# CSI2-IMX8M-EVK-2_Rev02.net
KiCad netlist of a schematic drawn in Altium Designer
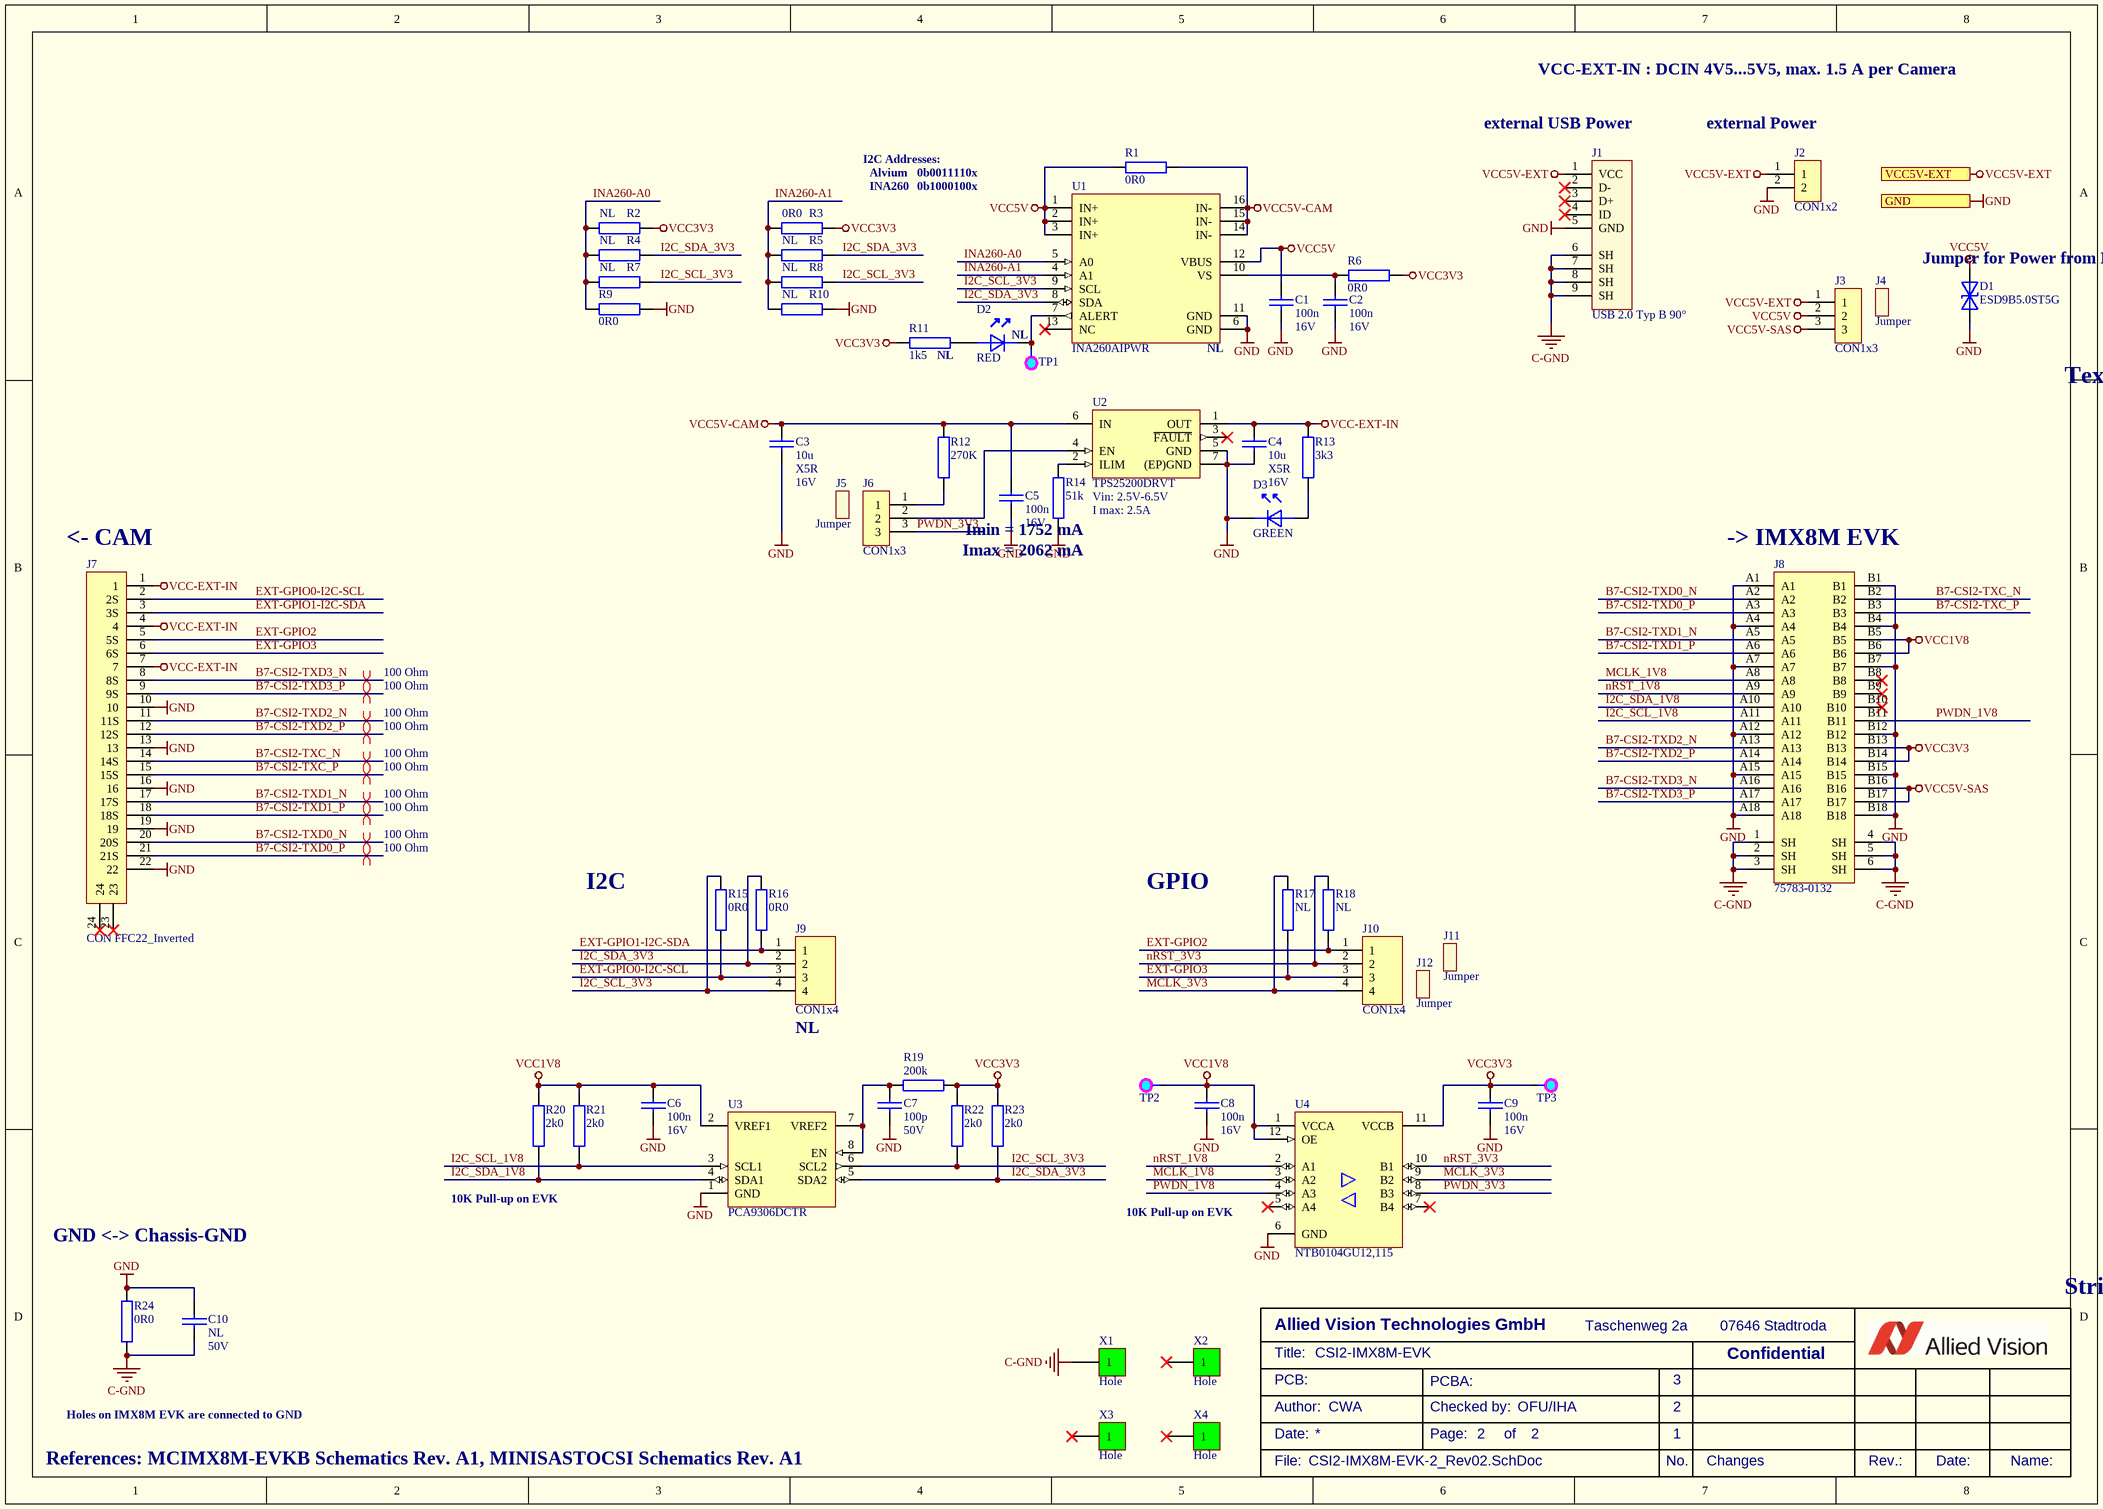
[diagram p0: CSI2-IMX8M-EVK-2_Rev02.SchDoc]

(export (version "E")
  (design (tool "Eeschema 10.0.6"))
  (components
    (comp (ref "C1")
      (value "100n")
      (footprint "C-0402_0.55")
      (description "Capacitor Ceramic SMD/0402/16V/X7R/10%")
      (fields
        (field (name "KHK PART NUMBER") "K8340114")
        (field (name "MANUFACTURER") "several")
        (field (name "VOLTAGE") "16V")
      )
      (libsource (lib "Passive") (part "C 100N 10% 16V X7R 402"))
    )
    (comp (ref "C2")
      (value "100n")
      (footprint "C-0402_0.55")
      (description "Capacitor Ceramic SMD/0402/16V/X7R/10%")
      (fields
        (field (name "KHK PART NUMBER") "K8340114")
        (field (name "MANUFACTURER") "several")
        (field (name "VOLTAGE") "16V")
      )
      (libsource (lib "Passive") (part "C 100N 10% 16V X7R 402"))
    )
    (comp (ref "C3")
      (value "10u")
      (footprint "C-0805_1.4")
      (description "Capacitor Ceramic SMD/0805/16V/X5R/10%")
      (fields
        (field (name "KHK PART NUMBER") "K8340151")
        (field (name "MANUFACTURER") "several")
        (field (name "DIELECTRIC") "X5R")
        (field (name "VOLTAGE") "16V")
      )
      (libsource (lib "Passive") (part "C 10U 16V X5R 0805"))
    )
    (comp (ref "C4")
      (value "10u")
      (footprint "C-0805_1.4")
      (description "Capacitor Ceramic SMD/0805/16V/X5R/10%")
      (fields
        (field (name "KHK PART NUMBER") "K8340151")
        (field (name "MANUFACTURER") "several")
        (field (name "DIELECTRIC") "X5R")
        (field (name "VOLTAGE") "16V")
      )
      (libsource (lib "Passive") (part "C 10U 16V X5R 0805"))
    )
    (comp (ref "C5")
      (value "100n")
      (footprint "C-0402_0.55")
      (description "Capacitor Ceramic SMD/0402/16V/X7R/10%")
      (fields
        (field (name "KHK PART NUMBER") "K8340114")
        (field (name "MANUFACTURER") "several")
        (field (name "VOLTAGE") "16V")
      )
      (libsource (lib "Passive") (part "C 100N 10% 16V X7R 402"))
    )
    (comp (ref "C6")
      (value "100n")
      (footprint "C-0402_0.55")
      (description "Capacitor Ceramic SMD/0402/16V/X7R/10%")
      (fields
        (field (name "KHK PART NUMBER") "K8340114")
        (field (name "MANUFACTURER") "several")
        (field (name "VOLTAGE") "16V")
      )
      (libsource (lib "Passive") (part "C 100N 10% 16V X7R 402"))
    )
    (comp (ref "C7")
      (value "100p")
      (footprint "C-0402_0.55")
      (description "Capacitor Ceramic SMD/0402/50V/X7R/10%")
      (fields
        (field (name "KHK PART NUMBER") "K8340145")
        (field (name "MANUFACTURER") "several")
        (field (name "VOLTAGE") "50V")
      )
      (libsource (lib "Passive") (part "C 100P 50V X7R 0402"))
    )
    (comp (ref "C8")
      (value "100n")
      (footprint "C-0402_0.55")
      (description "Capacitor Ceramic SMD/0402/16V/X7R/10%")
      (fields
        (field (name "KHK PART NUMBER") "K8340114")
        (field (name "MANUFACTURER") "several")
        (field (name "VOLTAGE") "16V")
      )
      (libsource (lib "Passive") (part "C 100N 10% 16V X7R 402"))
    )
    (comp (ref "C9")
      (value "100n")
      (footprint "C-0402_0.55")
      (description "Capacitor Ceramic SMD/0402/16V/X7R/10%")
      (fields
        (field (name "KHK PART NUMBER") "K8340114")
        (field (name "MANUFACTURER") "several")
        (field (name "VOLTAGE") "16V")
      )
      (libsource (lib "Passive") (part "C 100N 10% 16V X7R 402"))
    )
    (comp (ref "C10")
      (value "NL")
      (footprint "C-0603_1.0")
      (description "Capacitor Ceramic SMD/0603/50V/X7R/10%")
      (fields
        (field (name "MANUFACTURER") "several")
        (field (name "TOLERANCE") "10%")
        (field (name "VOLTAGE") "50V")
      )
      (libsource (lib "AVT_KHK_Lib") (part "C X 0603"))
    )
    (comp (ref "D1")
      (value "ESD9B5.0ST5G")
      (footprint "D-SOD923")
      (description "DIODE TVS; 400W; 5.8-7.8V; BIDIRECT")
      (fields (field (name "KHK PART NUMBER") "7250") (field (name "MANUFACTURER") "ON Semiconductor"))
      (libsource (lib "Bipolar") (part "D ESD9B5.0ST5G"))
    )
    (comp (ref "D2")
      (value "RED")
      (footprint "D-0603-LED")
      (description "Chip LED red 250mcd")
      (fields (field (name "KHK PART NUMBER") "8145") (field (name "MANUFACTURER") "Würth"))
      (libsource (lib "Bipolar") (part "D LED 0603 red"))
    )
    (comp (ref "D3")
      (value "GREEN")
      (footprint "D-0603-LED")
      (description "Chip LED green 430mcd")
      (fields (field (name "KHK PART NUMBER") "8172") (field (name "MANUFACTURER") "Würth"))
      (libsource (lib "Bipolar") (part "D LED 0603 green"))
    )
    (comp (ref "J1")
      (value "USB 2.0 Typ B 90°")
      (footprint "J-629105150521")
      (description "Micro USB 2.0 Typ B 90°")
      (fields (field (name "KHK PART NUMBER") "14360") (field (name "MANUFACTURER") "WE"))
      (libsource (lib "Connector") (part "CON USB 2.0 Typ B 90°"))
    )
    (comp (ref "J2")
      (value "CON1x2")
      (footprint "CON 1x2 RM2.54")
      (fields (field (name "MANUFACTURER") "several") (field (name "KHK PART NUMBER") "15337"))
      (libsource (lib "Connector") (part "CON 1x2 2.54 several"))
    )
    (comp (ref "J3")
      (value "CON1x3")
      (footprint "CON 1x3 RM2.54")
      (fields (field (name "MANUFACTURER") "several") (field (name "KHK PART NUMBER") "15338"))
      (libsource (lib "Connector") (part "CON 1x3 2.54 several"))
    )
    (comp (ref "J4")
      (value "Jumper")
      (footprint "J-JUMPER-2.54")
      (description "CON/JUMPER/STC02SYAN; 2-pin; 2.54mm; 3A; FEMALE; VERTICAL; BLACK")
      (fields (field (name "KHK PART NUMBER") "13444") (field (name "MANUFACTURER") "several"))
      (libsource (lib "Connector") (part "CON Jumper 2.54mm"))
    )
    (comp (ref "J5")
      (value "Jumper")
      (footprint "J-JUMPER-2.54")
      (description "CON/JUMPER/STC02SYAN; 2-pin; 2.54mm; 3A; FEMALE; VERTICAL; BLACK")
      (fields (field (name "KHK PART NUMBER") "13444") (field (name "MANUFACTURER") "several"))
      (libsource (lib "") (part "CON Jumper 2.54mm_1"))
    )
    (comp (ref "J6")
      (value "CON1x3")
      (footprint "CON 1x3 RM2.54")
      (fields (field (name "MANUFACTURER") "several") (field (name "KHK PART NUMBER") "15338"))
      (libsource (lib "") (part "CON 1x3 2.54 several_1"))
    )
    (comp (ref "J7")
      (value "CON FFC22_Inverted")
      (footprint "J-FH55-22S-0.5SH - Inverted Pins")
      (description "FFC Connector 0.5mm shielded")
      (fields
        (field (name "KHK PART NUMBER") "10357")
        (field (name "MANUFACTURER PART NUMBER") "FH55-22S-0.5SH")
      )
      (libsource (lib "Connector") (part "CON FFC22_FH55-22S-0.5SH_Inverted"))
    )
    (comp (ref "J8")
      (value "75783-0132")
      (footprint "J-757830132")
      (description "36pin MINI SAS iPass Receptacle 0.8mm pitch")
      (fields (field (name "MANUFACTURER") "Molex") (field (name "KHK PART NUMBER") "16136"))
      (libsource (lib "Connector") (part "CON Molex 75783-0132"))
    )
    (comp (ref "J9")
      (value "CON1x4")
      (footprint "CON 1x4 RM2.54")
      (fields (field (name "MANUFACTURER") "several") (field (name "KHK PART NUMBER") "15343"))
      (libsource (lib "Connector") (part "CON 1x4 2.54 several"))
    )
    (comp (ref "J10")
      (value "CON1x4")
      (footprint "CON 1x4 RM2.54")
      (fields (field (name "MANUFACTURER") "several") (field (name "KHK PART NUMBER") "15343"))
      (libsource (lib "Connector") (part "CON 1x4 2.54 several"))
    )
    (comp (ref "J11")
      (value "Jumper")
      (footprint "J-JUMPER-2.54")
      (description "CON/JUMPER/STC02SYAN; 2-pin; 2.54mm; 3A; FEMALE; VERTICAL; BLACK")
      (fields (field (name "KHK PART NUMBER") "13444") (field (name "MANUFACTURER") "several"))
      (libsource (lib "Connector") (part "CON Jumper 2.54mm"))
    )
    (comp (ref "J12")
      (value "Jumper")
      (footprint "J-JUMPER-2.54")
      (description "CON/JUMPER/STC02SYAN; 2-pin; 2.54mm; 3A; FEMALE; VERTICAL; BLACK")
      (fields (field (name "KHK PART NUMBER") "13444") (field (name "MANUFACTURER") "several"))
      (libsource (lib "Connector") (part "CON Jumper 2.54mm"))
    )
    (comp (ref "R1")
      (value "0R0")
      (footprint "R-0603_0.6")
      (description "Standard Resistor SMD/0603/1%/100mW/TK200")
      (fields (field (name "KHK PART NUMBER") "K8250041") (field (name "MANUFACTURER") "several"))
      (libsource (lib "AVT_KHK_Lib") (part "R 0R0 1% 0603"))
    )
    (comp (ref "R2")
      (value "NL")
      (footprint "R-0603_0.6")
      (description "Standard Resistor SMD/0603/1%/100mW/TK200")
      (fields (field (name "TOLERANCE") "1%"))
      (libsource (lib "AVT_KHK_Lib") (part "R X 0603"))
    )
    (comp (ref "R3")
      (value "0R0")
      (footprint "R-0603_0.6")
      (description "Standard Resistor SMD/0603/1%/100mW/TK200")
      (fields (field (name "KHK PART NUMBER") "K8250041") (field (name "MANUFACTURER") "several"))
      (libsource (lib "Passive") (part "R 0R0 1% 0603"))
    )
    (comp (ref "R4")
      (value "NL")
      (footprint "R-0603_0.6")
      (description "Standard Resistor SMD/0603/1%/100mW/TK200")
      (fields (field (name "TOLERANCE") "1%"))
      (libsource (lib "AVT_KHK_Lib") (part "R X 0603"))
    )
    (comp (ref "R5")
      (value "NL")
      (footprint "R-0603_0.6")
      (description "Standard Resistor SMD/0603/1%/100mW/TK200")
      (fields (field (name "TOLERANCE") "1%"))
      (libsource (lib "AVT_KHK_Lib") (part "R X 0603"))
    )
    (comp (ref "R6")
      (value "0R0")
      (footprint "R-0603_0.6")
      (description "Standard Resistor SMD/0603/1%/100mW/TK200")
      (fields (field (name "KHK PART NUMBER") "K8250041") (field (name "MANUFACTURER") "several"))
      (libsource (lib "Passive") (part "R 0R0 1% 0603"))
    )
    (comp (ref "R7")
      (value "NL")
      (footprint "R-0603_0.6")
      (description "Standard Resistor SMD/0603/1%/100mW/TK200")
      (fields (field (name "TOLERANCE") "1%"))
      (libsource (lib "AVT_KHK_Lib") (part "R X 0603"))
    )
    (comp (ref "R8")
      (value "NL")
      (footprint "R-0603_0.6")
      (description "Standard Resistor SMD/0603/1%/100mW/TK200")
      (fields (field (name "TOLERANCE") "1%"))
      (libsource (lib "AVT_KHK_Lib") (part "R X 0603"))
    )
    (comp (ref "R9")
      (value "0R0")
      (footprint "R-0603_0.6")
      (description "Standard Resistor SMD/0603/1%/100mW/TK200")
      (fields (field (name "KHK PART NUMBER") "K8250041") (field (name "MANUFACTURER") "several"))
      (libsource (lib "Passive") (part "R 0R0 1% 0603"))
    )
    (comp (ref "R10")
      (value "NL")
      (footprint "R-0603_0.6")
      (description "Standard Resistor SMD/0603/1%/100mW/TK200")
      (fields (field (name "TOLERANCE") "1%"))
      (libsource (lib "AVT_KHK_Lib") (part "R X 0603"))
    )
    (comp (ref "R11")
      (value "1k5")
      (footprint "R-0402_0.4")
      (description "Standard Resistor SMD/0402/1%/63mW/TK100")
      (fields (field (name "KHK PART NUMBER") "K8250358") (field (name "MANUFACTURER") "several"))
      (libsource (lib "Passive") (part "R 1K5 1% 0402"))
    )
    (comp (ref "R12")
      (value "270K")
      (footprint "R-0402_0.4")
      (description "Standard Resistor SMD/0402/1%/63mW/TK100")
      (fields (field (name "KHK PART NUMBER") "3875") (field (name "MANUFACTURER") "several"))
      (libsource (lib "Passive") (part "R 270K 1% 0402"))
    )
    (comp (ref "R13")
      (value "3k3")
      (footprint "R-0402_0.4")
      (description "Standard Resistor SMD/0402/1%/63mW/TK100")
      (fields (field (name "KHK PART NUMBER") "K8250347") (field (name "MANUFACTURER") "several"))
      (libsource (lib "Passive") (part "R 3k3 1% 0402"))
    )
    (comp (ref "R14")
      (value "51k")
      (footprint "R-0402_0.4")
      (description "Standard Resistor SMD/0402/1%/63mW/TK100")
      (fields (field (name "KHK PART NUMBER") "K8250273") (field (name "MANUFACTURER") "several"))
      (libsource (lib "Passive") (part "R 51K 1% 0402"))
    )
    (comp (ref "R15")
      (value "0R0")
      (footprint "R-0603_0.6")
      (description "Standard Resistor SMD/0603/1%/100mW/TK200")
      (fields (field (name "KHK PART NUMBER") "K8250041") (field (name "MANUFACTURER") "several"))
      (libsource (lib "Passive") (part "R 0R0 1% 0603"))
    )
    (comp (ref "R16")
      (value "0R0")
      (footprint "R-0603_0.6")
      (description "Standard Resistor SMD/0603/1%/100mW/TK200")
      (fields (field (name "KHK PART NUMBER") "K8250041") (field (name "MANUFACTURER") "several"))
      (libsource (lib "Passive") (part "R 0R0 1% 0603"))
    )
    (comp (ref "R17")
      (value "NL")
      (footprint "R-0603_0.6")
      (description "Standard Resistor SMD/0603/1%/100mW/TK200")
      (fields (field (name "TOLERANCE") "1%"))
      (libsource (lib "AVT_KHK_Lib") (part "R X 0603"))
    )
    (comp (ref "R18")
      (value "NL")
      (footprint "R-0603_0.6")
      (description "Standard Resistor SMD/0603/1%/100mW/TK200")
      (fields (field (name "TOLERANCE") "1%"))
      (libsource (lib "AVT_KHK_Lib") (part "R X 0603"))
    )
    (comp (ref "R19")
      (value "200k")
      (footprint "R-0402_0.4")
      (description "Standard Resistor SMD/0402/1%/63mW/TK100")
      (fields (field (name "KHK PART NUMBER") "K8250280") (field (name "MANUFACTURER") "several"))
      (libsource (lib "Passive") (part "R 200K 1% 0402"))
    )
    (comp (ref "R20")
      (value "2k0")
      (footprint "R-0402_0.4")
      (description "Standard Resistor SMD/0402/1%/63mW/TK100")
      (fields (field (name "KHK PART NUMBER") "K8250311") (field (name "MANUFACTURER") "several"))
      (libsource (lib "Passive") (part "R 2k0 1% 0402"))
    )
    (comp (ref "R21")
      (value "2k0")
      (footprint "R-0402_0.4")
      (description "Standard Resistor SMD/0402/1%/63mW/TK100")
      (fields (field (name "KHK PART NUMBER") "K8250311") (field (name "MANUFACTURER") "several"))
      (libsource (lib "Passive") (part "R 2k0 1% 0402"))
    )
    (comp (ref "R22")
      (value "2k0")
      (footprint "R-0402_0.4")
      (description "Standard Resistor SMD/0402/1%/63mW/TK100")
      (fields (field (name "KHK PART NUMBER") "K8250311") (field (name "MANUFACTURER") "several"))
      (libsource (lib "Passive") (part "R 2k0 1% 0402"))
    )
    (comp (ref "R23")
      (value "2k0")
      (footprint "R-0402_0.4")
      (description "Standard Resistor SMD/0402/1%/63mW/TK100")
      (fields (field (name "KHK PART NUMBER") "K8250311") (field (name "MANUFACTURER") "several"))
      (libsource (lib "Passive") (part "R 2k0 1% 0402"))
    )
    (comp (ref "R24")
      (value "0R0")
      (footprint "R-0603_0.6")
      (description "Standard Resistor SMD/0603/1%/100mW/TK200")
      (fields (field (name "KHK PART NUMBER") "K8250041") (field (name "MANUFACTURER") "several"))
      (libsource (lib "Passive") (part "R 0R0 1% 0603"))
    )
    (comp (ref "TP1")
      (value "TP")
      (footprint "TP_16_10")
      (description "Testpoint: Pad=1,6mm; Hole=1,0mm")
      (libsource (lib "AVT_KHK_Lib") (part "TP_16_10"))
    )
    (comp (ref "TP2")
      (value "TP")
      (footprint "TP_16_10")
      (description "Testpoint: Pad=1,6mm; Hole=1,0mm")
      (libsource (lib "AVT_KHK_Lib") (part "TP_16_10"))
    )
    (comp (ref "TP3")
      (value "TP")
      (footprint "TP_16_10")
      (description "Testpoint: Pad=1,6mm; Hole=1,0mm")
      (libsource (lib "AVT_KHK_Lib") (part "TP_16_10"))
    )
    (comp (ref "U1")
      (value "INA260AIPWR")
      (footprint "IC-TSSOP16 6.4x5.1x1.2")
      (description "IC/PWR/CURR SHUNT MONITOR/2.7-5.5V;4.5mR/TSSOP16/5.0x4.4x1.2mm")
      (fields (field (name "KHK PART NUMBER") "16206") (field (name "MANUFACTURER") "TI"))
      (libsource (lib "Power") (part "IC INA260"))
    )
    (comp (ref "U2")
      (value "TPS25200DRVT")
      (footprint "IC-DFN06_2.0x2.0x0.8")
      (description "IC/PWR/LOADSW;2V5-6V5;2A5;0R099/6-WDFN/2x2x0.8mm")
      (fields
        (field (name "KHK PART NUMBER") "14277")
        (field (name "MANUFACTURER") "Texas Instruments")
        (field (name "VIN") "2.5V-6.5V")
        (field (name "I MAX") "2.5A")
      )
      (libsource (lib "Power") (part "IC  TPS25200DRVT"))
    )
    (comp (ref "U3")
      (value "PCA9306DCTR")
      (footprint "IC-TSSOP8_3.15x4.25x1.3")
      (description "IC/LOGIC/LEVELSHIFTER;I2C;AUTO-DIR;1V2-5V/SSOP-8/4.25x3.15x1.3mm")
      (fields (field (name "KHK PART NUMBER") "9555") (field (name "MANUFACTURER") "TI"))
      (libsource (lib "Logic") (part "IC PCA9306DCTR"))
    )
    (comp (ref "U4")
      (value "NTB0104GU12,115")
      (footprint "IC-XQFN12_1.7x2x0.5")
      (description "IC/LOGIC/Levelshifter;Auto-Dir;Bidirectional;Push-Pull;-40-+125°C/")
      (fields (field (name "MANUFACTURER") "NXP") (field (name "KHK PART NUMBER") "14383"))
      (libsource (lib "Logic") (part "IC NTB0104GU12,115"))
    )
    (comp (ref "X1")
      (value "Hole")
      (footprint "HOLE-2.6-5.0-DK")
      (description "HOLE M2.5")
      (libsource (lib "AVT_KHK_Lib") (part "PCB HOLE M2.5-5-DK"))
    )
    (comp (ref "X2")
      (value "Hole")
      (footprint "HOLE-2.6-5.0-DK")
      (description "HOLE M2.5")
      (libsource (lib "AVT_KHK_Lib") (part "PCB HOLE M2.5-5-DK"))
    )
    (comp (ref "X3")
      (value "Hole")
      (footprint "HOLE-2.6-5.0-DK")
      (description "HOLE M2.5")
      (libsource (lib "AVT_KHK_Lib") (part "PCB HOLE M2.5-5-DK"))
    )
    (comp (ref "X4")
      (value "Hole")
      (footprint "HOLE-2.6-5.0-DK")
      (description "HOLE M2.5")
      (libsource (lib "AVT_KHK_Lib") (part "PCB HOLE M2.5-5-DK"))
    )
  )
  (nets
    (net (code "1") (name "/B7-CSI2-TXC_N") (class "Default")
      (node (ref "J7") (pin "14") (pinfunction "14S_14") (pintype "passive"))
      (node (ref "J8") (pin "B2") (pinfunction "B2_B2") (pintype "passive"))
    )
    (net (code "2") (name "/B7-CSI2-TXC_P") (class "Default")
      (node (ref "J7") (pin "15") (pinfunction "15S_15") (pintype "passive"))
      (node (ref "J8") (pin "B3") (pinfunction "B3_B3") (pintype "passive"))
    )
    (net (code "3") (name "/B7-CSI2-TXD0_N") (class "Default")
      (node (ref "J7") (pin "20") (pinfunction "20S_20") (pintype "passive"))
      (node (ref "J8") (pin "A2") (pinfunction "A2_A2") (pintype "passive"))
    )
    (net (code "4") (name "/B7-CSI2-TXD0_P") (class "Default")
      (node (ref "J7") (pin "21") (pinfunction "21S_21") (pintype "passive"))
      (node (ref "J8") (pin "A3") (pinfunction "A3_A3") (pintype "passive"))
    )
    (net (code "5") (name "/B7-CSI2-TXD1_N") (class "Default")
      (node (ref "J7") (pin "17") (pinfunction "17S_17") (pintype "passive"))
      (node (ref "J8") (pin "A5") (pinfunction "A5_A5") (pintype "passive"))
    )
    (net (code "6") (name "/B7-CSI2-TXD1_P") (class "Default")
      (node (ref "J7") (pin "18") (pinfunction "18S_18") (pintype "passive"))
      (node (ref "J8") (pin "A6") (pinfunction "A6_A6") (pintype "passive"))
    )
    (net (code "7") (name "/B7-CSI2-TXD2_N") (class "Default")
      (node (ref "J7") (pin "11") (pinfunction "11S_11") (pintype "passive"))
      (node (ref "J8") (pin "A13") (pinfunction "A13_A13") (pintype "passive"))
    )
    (net (code "8") (name "/B7-CSI2-TXD2_P") (class "Default")
      (node (ref "J7") (pin "12") (pinfunction "12S_12") (pintype "passive"))
      (node (ref "J8") (pin "A14") (pinfunction "A14_A14") (pintype "passive"))
    )
    (net (code "9") (name "/B7-CSI2-TXD3_N") (class "Default")
      (node (ref "J7") (pin "8") (pinfunction "8S_8") (pintype "passive"))
      (node (ref "J8") (pin "A16") (pinfunction "A16_A16") (pintype "passive"))
    )
    (net (code "10") (name "/B7-CSI2-TXD3_P") (class "Default")
      (node (ref "J7") (pin "9") (pinfunction "9S_9") (pintype "passive"))
      (node (ref "J8") (pin "A17") (pinfunction "A17_A17") (pintype "passive"))
    )
    (net (code "11") (name "/EXT-GPIO0-I2C-SCL") (class "Default")
      (node (ref "J7") (pin "2") (pinfunction "2S_2") (pintype "passive"))
      (node (ref "J9") (pin "3") (pinfunction "3_3") (pintype "passive"))
      (node (ref "R15") (pin "1") (pinfunction "1_1") (pintype "passive"))
    )
    (net (code "12") (name "/EXT-GPIO1-I2C-SDA") (class "Default")
      (node (ref "J7") (pin "3") (pinfunction "3S_3") (pintype "passive"))
      (node (ref "J9") (pin "1") (pinfunction "1_1") (pintype "passive"))
      (node (ref "R16") (pin "1") (pinfunction "1_1") (pintype "passive"))
    )
    (net (code "13") (name "/EXT-GPIO2") (class "Default")
      (node (ref "J10") (pin "1") (pinfunction "1_1") (pintype "passive"))
      (node (ref "J7") (pin "5") (pinfunction "5S_5") (pintype "passive"))
      (node (ref "R18") (pin "1") (pinfunction "1_1") (pintype "passive"))
    )
    (net (code "14") (name "/EXT-GPIO3") (class "Default")
      (node (ref "J10") (pin "3") (pinfunction "3_3") (pintype "passive"))
      (node (ref "J7") (pin "6") (pinfunction "6S_6") (pintype "passive"))
      (node (ref "R17") (pin "1") (pinfunction "1_1") (pintype "passive"))
    )
    (net (code "15") (name "/I2C_SCL_1V8") (class "Default")
      (node (ref "J8") (pin "A11") (pinfunction "A11_A11") (pintype "passive"))
      (node (ref "R21") (pin "2") (pinfunction "2_2") (pintype "passive"))
      (node (ref "U3") (pin "3") (pinfunction "SCL1_3") (pintype "input"))
    )
    (net (code "16") (name "/I2C_SCL_3V3") (class "Default")
      (node (ref "J9") (pin "4") (pinfunction "4_4") (pintype "passive"))
      (node (ref "R15") (pin "2") (pinfunction "2_2") (pintype "passive"))
      (node (ref "R22") (pin "1") (pinfunction "1_1") (pintype "passive"))
      (node (ref "R7") (pin "1") (pinfunction "1_1") (pintype "passive"))
      (node (ref "R8") (pin "1") (pinfunction "1_1") (pintype "passive"))
      (node (ref "U1") (pin "9") (pinfunction "SCL_9") (pintype "input"))
      (node (ref "U3") (pin "6") (pinfunction "SCL2_6") (pintype "output"))
    )
    (net (code "17") (name "/I2C_SDA_1V8") (class "Default")
      (node (ref "J8") (pin "A10") (pinfunction "A10_A10") (pintype "passive"))
      (node (ref "R20") (pin "2") (pinfunction "2_2") (pintype "passive"))
      (node (ref "U3") (pin "4") (pinfunction "SDA1_4") (pintype "bidirectional"))
    )
    (net (code "18") (name "/I2C_SDA_3V3") (class "Default")
      (node (ref "J9") (pin "2") (pinfunction "2_2") (pintype "passive"))
      (node (ref "R16") (pin "2") (pinfunction "2_2") (pintype "passive"))
      (node (ref "R23") (pin "1") (pinfunction "1_1") (pintype "passive"))
      (node (ref "R4") (pin "1") (pinfunction "1_1") (pintype "passive"))
      (node (ref "R5") (pin "1") (pinfunction "1_1") (pintype "passive"))
      (node (ref "U1") (pin "8") (pinfunction "SDA_8") (pintype "bidirectional"))
      (node (ref "U3") (pin "5") (pinfunction "SDA2_5") (pintype "bidirectional"))
    )
    (net (code "19") (name "/INA260-A0") (class "Default")
      (node (ref "R2") (pin "2") (pinfunction "2_2") (pintype "passive"))
      (node (ref "R4") (pin "2") (pinfunction "2_2") (pintype "passive"))
      (node (ref "R7") (pin "2") (pinfunction "2_2") (pintype "passive"))
      (node (ref "R9") (pin "2") (pinfunction "2_2") (pintype "passive"))
      (node (ref "U1") (pin "5") (pinfunction "A0_5") (pintype "input"))
    )
    (net (code "20") (name "/INA260-A1") (class "Default")
      (node (ref "R10") (pin "2") (pinfunction "2_2") (pintype "passive"))
      (node (ref "R3") (pin "2") (pinfunction "2_2") (pintype "passive"))
      (node (ref "R5") (pin "2") (pinfunction "2_2") (pintype "passive"))
      (node (ref "R8") (pin "2") (pinfunction "2_2") (pintype "passive"))
      (node (ref "U1") (pin "4") (pinfunction "A1_4") (pintype "input"))
    )
    (net (code "21") (name "/MCLK_1V8") (class "Default")
      (node (ref "J8") (pin "A8") (pinfunction "A8_A8") (pintype "passive"))
      (node (ref "U4") (pin "3") (pinfunction "A2_3") (pintype "bidirectional"))
    )
    (net (code "22") (name "/MCLK_3V3") (class "Default")
      (node (ref "J10") (pin "4") (pinfunction "4_4") (pintype "passive"))
      (node (ref "R17") (pin "2") (pinfunction "2_2") (pintype "passive"))
      (node (ref "U4") (pin "9") (pinfunction "B2_9") (pintype "bidirectional"))
    )
    (net (code "23") (name "/PWDN_1V8") (class "Default")
      (node (ref "J8") (pin "B11") (pinfunction "B11_B11") (pintype "passive"))
      (node (ref "U4") (pin "4") (pinfunction "A3_4") (pintype "bidirectional"))
    )
    (net (code "24") (name "/PWDN_3V3") (class "Default")
      (node (ref "J6") (pin "3") (pinfunction "3_3") (pintype "passive"))
      (node (ref "U4") (pin "8") (pinfunction "B3_8") (pintype "bidirectional"))
    )
    (net (code "25") (name "/nRST_1V8") (class "Default")
      (node (ref "J8") (pin "A9") (pinfunction "A9_A9") (pintype "passive"))
      (node (ref "U4") (pin "2") (pinfunction "A1_2") (pintype "bidirectional"))
    )
    (net (code "26") (name "/nRST_3V3") (class "Default")
      (node (ref "J10") (pin "2") (pinfunction "2_2") (pintype "passive"))
      (node (ref "R18") (pin "2") (pinfunction "2_2") (pintype "passive"))
      (node (ref "U4") (pin "10") (pinfunction "B1_10") (pintype "bidirectional"))
    )
    (net (code "27") (name "C-GND") (class "Default")
      (node (ref "C10") (pin "2") (pinfunction "2_2") (pintype "passive"))
      (node (ref "J1") (pin "6") (pinfunction "SH_6") (pintype "passive"))
      (node (ref "J1") (pin "7") (pinfunction "SH_7") (pintype "passive"))
      (node (ref "J1") (pin "8") (pinfunction "SH_8") (pintype "passive"))
      (node (ref "J1") (pin "9") (pinfunction "SH_9") (pintype "passive"))
      (node (ref "J8") (pin "1") (pinfunction "SH_1") (pintype "passive"))
      (node (ref "J8") (pin "2") (pinfunction "SH_2") (pintype "passive"))
      (node (ref "J8") (pin "3") (pinfunction "SH_3") (pintype "passive"))
      (node (ref "J8") (pin "4") (pinfunction "SH_4") (pintype "passive"))
      (node (ref "J8") (pin "5") (pinfunction "SH_5") (pintype "passive"))
      (node (ref "J8") (pin "6") (pinfunction "SH_6") (pintype "passive"))
      (node (ref "R24") (pin "1") (pinfunction "1_1") (pintype "passive"))
      (node (ref "X1") (pin "1") (pinfunction "1_1") (pintype "passive"))
    )
    (net (code "28") (name "GND") (class "Default")
      (node (ref "C1") (pin "2") (pinfunction "2_2") (pintype "passive"))
      (node (ref "C10") (pin "1") (pinfunction "1_1") (pintype "passive"))
      (node (ref "C2") (pin "2") (pinfunction "2_2") (pintype "passive"))
      (node (ref "C3") (pin "2") (pinfunction "2_2") (pintype "passive"))
      (node (ref "C4") (pin "2") (pinfunction "2_2") (pintype "passive"))
      (node (ref "C5") (pin "2") (pinfunction "2_2") (pintype "passive"))
      (node (ref "C6") (pin "2") (pinfunction "2_2") (pintype "passive"))
      (node (ref "C7") (pin "2") (pinfunction "2_2") (pintype "passive"))
      (node (ref "C8") (pin "2") (pinfunction "2_2") (pintype "passive"))
      (node (ref "C9") (pin "2") (pinfunction "2_2") (pintype "passive"))
      (node (ref "D1") (pin "A") (pinfunction "A_A") (pintype "passive"))
      (node (ref "D3") (pin "K") (pinfunction "2_K") (pintype "passive"))
      (node (ref "J1") (pin "5") (pinfunction "GND_5") (pintype "passive"))
      (node (ref "J2") (pin "2") (pinfunction "2_2") (pintype "passive"))
      (node (ref "J7") (pin "10") (pinfunction "10_10") (pintype "passive"))
      (node (ref "J7") (pin "13") (pinfunction "13_13") (pintype "passive"))
      (node (ref "J7") (pin "16") (pinfunction "16_16") (pintype "passive"))
      (node (ref "J7") (pin "19") (pinfunction "19_19") (pintype "passive"))
      (node (ref "J7") (pin "22") (pinfunction "22_22") (pintype "passive"))
      (node (ref "J8") (pin "A1") (pinfunction "A1_A1") (pintype "passive"))
      (node (ref "J8") (pin "A12") (pinfunction "A12_A12") (pintype "passive"))
      (node (ref "J8") (pin "A15") (pinfunction "A15_A15") (pintype "passive"))
      (node (ref "J8") (pin "A18") (pinfunction "A18_A18") (pintype "passive"))
      (node (ref "J8") (pin "A4") (pinfunction "A4_A4") (pintype "passive"))
      (node (ref "J8") (pin "A7") (pinfunction "A7_A7") (pintype "passive"))
      (node (ref "J8") (pin "B1") (pinfunction "B1_B1") (pintype "passive"))
      (node (ref "J8") (pin "B12") (pinfunction "B12_B12") (pintype "passive"))
      (node (ref "J8") (pin "B15") (pinfunction "B15_B15") (pintype "passive"))
      (node (ref "J8") (pin "B18") (pinfunction "B18_B18") (pintype "passive"))
      (node (ref "J8") (pin "B4") (pinfunction "B4_B4") (pintype "passive"))
      (node (ref "J8") (pin "B7") (pinfunction "B7_B7") (pintype "passive"))
      (node (ref "R10") (pin "1") (pinfunction "1_1") (pintype "passive"))
      (node (ref "R14") (pin "1") (pinfunction "1_1") (pintype "passive"))
      (node (ref "R24") (pin "2") (pinfunction "2_2") (pintype "passive"))
      (node (ref "R9") (pin "1") (pinfunction "1_1") (pintype "passive"))
      (node (ref "U1") (pin "11") (pinfunction "GND_11") (pintype "power_in"))
      (node (ref "U1") (pin "6") (pinfunction "GND_6") (pintype "power_in"))
      (node (ref "U2") (pin "5") (pinfunction "GND_5") (pintype "power_in"))
      (node (ref "U2") (pin "7") (pinfunction "(EP)GND_7") (pintype "power_in"))
      (node (ref "U3") (pin "1") (pinfunction "GND_1") (pintype "power_in"))
      (node (ref "U4") (pin "6") (pinfunction "GND_6") (pintype "power_in"))
    )
    (net (code "29") (name "Net-(D2-1)") (class "Default")
      (node (ref "D2") (pin "A") (pinfunction "1_A") (pintype "passive"))
      (node (ref "R11") (pin "2") (pinfunction "2_2") (pintype "passive"))
    )
    (net (code "30") (name "Net-(D2-2)") (class "Default")
      (node (ref "D2") (pin "K") (pinfunction "2_K") (pintype "passive"))
      (node (ref "TP1") (pin "1") (pinfunction "1_1") (pintype "passive"))
      (node (ref "U1") (pin "7") (pinfunction "ALERT_7") (pintype "output"))
    )
    (net (code "31") (name "Net-(D3-1)") (class "Default")
      (node (ref "D3") (pin "A") (pinfunction "1_A") (pintype "passive"))
      (node (ref "R13") (pin "2") (pinfunction "2_2") (pintype "passive"))
    )
    (net (code "32") (name "Net-(J6-Pad1)") (class "Default")
      (node (ref "J6") (pin "1") (pinfunction "1_1") (pintype "passive"))
      (node (ref "R12") (pin "2") (pinfunction "2_2") (pintype "passive"))
    )
    (net (code "33") (name "Net-(U1-VS)") (class "Default")
      (node (ref "C2") (pin "1") (pinfunction "1_1") (pintype "passive"))
      (node (ref "R6") (pin "2") (pinfunction "2_2") (pintype "passive"))
      (node (ref "U1") (pin "10") (pinfunction "VS_10") (pintype "power_in"))
    )
    (net (code "34") (name "Net-(U2-EN)") (class "Default")
      (node (ref "J6") (pin "2") (pinfunction "2_2") (pintype "passive"))
      (node (ref "U2") (pin "4") (pinfunction "EN_4") (pintype "input"))
    )
    (net (code "35") (name "Net-(U2-ILIM)") (class "Default")
      (node (ref "R14") (pin "2") (pinfunction "2_2") (pintype "passive"))
      (node (ref "U2") (pin "2") (pinfunction "ILIM_2") (pintype "input"))
    )
    (net (code "36") (name "Net-(U3-EN)") (class "Default")
      (node (ref "C7") (pin "1") (pinfunction "1_1") (pintype "passive"))
      (node (ref "R19") (pin "1") (pinfunction "1_1") (pintype "passive"))
      (node (ref "U3") (pin "7") (pinfunction "VREF2_7") (pintype "power_in"))
      (node (ref "U3") (pin "8") (pinfunction "EN_8") (pintype "input"))
    )
    (net (code "37") (name "VCC-EXT-IN") (class "Default")
      (node (ref "C4") (pin "1") (pinfunction "1_1") (pintype "passive"))
      (node (ref "J7") (pin "1") (pinfunction "1_1") (pintype "passive"))
      (node (ref "J7") (pin "4") (pinfunction "4_4") (pintype "passive"))
      (node (ref "J7") (pin "7") (pinfunction "7_7") (pintype "passive"))
      (node (ref "R13") (pin "1") (pinfunction "1_1") (pintype "passive"))
      (node (ref "U2") (pin "1") (pinfunction "OUT_1") (pintype "power_in"))
    )
    (net (code "38") (name "VCC1V8") (class "Default")
      (node (ref "C6") (pin "1") (pinfunction "1_1") (pintype "passive"))
      (node (ref "C8") (pin "1") (pinfunction "1_1") (pintype "passive"))
      (node (ref "J8") (pin "B5") (pinfunction "B5_B5") (pintype "passive"))
      (node (ref "J8") (pin "B6") (pinfunction "B6_B6") (pintype "passive"))
      (node (ref "R20") (pin "1") (pinfunction "1_1") (pintype "passive"))
      (node (ref "R21") (pin "1") (pinfunction "1_1") (pintype "passive"))
      (node (ref "TP2") (pin "1") (pinfunction "1_1") (pintype "passive"))
      (node (ref "U3") (pin "2") (pinfunction "VREF1_2") (pintype "power_in"))
      (node (ref "U4") (pin "1") (pinfunction "VCCA_1") (pintype "power_in"))
      (node (ref "U4") (pin "12") (pinfunction "OE_12") (pintype "input"))
    )
    (net (code "39") (name "VCC3V3") (class "Default")
      (node (ref "C9") (pin "1") (pinfunction "1_1") (pintype "passive"))
      (node (ref "J8") (pin "B13") (pinfunction "B13_B13") (pintype "passive"))
      (node (ref "J8") (pin "B14") (pinfunction "B14_B14") (pintype "passive"))
      (node (ref "R11") (pin "1") (pinfunction "1_1") (pintype "passive"))
      (node (ref "R19") (pin "2") (pinfunction "2_2") (pintype "passive"))
      (node (ref "R2") (pin "1") (pinfunction "1_1") (pintype "passive"))
      (node (ref "R22") (pin "2") (pinfunction "2_2") (pintype "passive"))
      (node (ref "R23") (pin "2") (pinfunction "2_2") (pintype "passive"))
      (node (ref "R3") (pin "1") (pinfunction "1_1") (pintype "passive"))
      (node (ref "R6") (pin "1") (pinfunction "1_1") (pintype "passive"))
      (node (ref "TP3") (pin "1") (pinfunction "1_1") (pintype "passive"))
      (node (ref "U4") (pin "11") (pinfunction "VCCB_11") (pintype "power_in"))
    )
    (net (code "40") (name "VCC5V") (class "Default")
      (node (ref "C1") (pin "1") (pinfunction "1_1") (pintype "passive"))
      (node (ref "D1") (pin "K") (pinfunction "K_K") (pintype "passive"))
      (node (ref "J3") (pin "2") (pinfunction "2_2") (pintype "passive"))
      (node (ref "R1") (pin "2") (pinfunction "2_2") (pintype "passive"))
      (node (ref "U1") (pin "1") (pinfunction "IN+_1") (pintype "passive"))
      (node (ref "U1") (pin "12") (pinfunction "VBUS_12") (pintype "power_in"))
      (node (ref "U1") (pin "2") (pinfunction "IN+_2") (pintype "passive"))
      (node (ref "U1") (pin "3") (pinfunction "IN+_3") (pintype "passive"))
    )
    (net (code "41") (name "VCC5V-CAM") (class "Default")
      (node (ref "C3") (pin "1") (pinfunction "1_1") (pintype "passive"))
      (node (ref "C5") (pin "1") (pinfunction "1_1") (pintype "passive"))
      (node (ref "R1") (pin "1") (pinfunction "1_1") (pintype "passive"))
      (node (ref "R12") (pin "1") (pinfunction "1_1") (pintype "passive"))
      (node (ref "U1") (pin "14") (pinfunction "IN-_14") (pintype "passive"))
      (node (ref "U1") (pin "15") (pinfunction "IN-_15") (pintype "passive"))
      (node (ref "U1") (pin "16") (pinfunction "IN-_16") (pintype "passive"))
      (node (ref "U2") (pin "6") (pinfunction "IN_6") (pintype "power_in"))
    )
    (net (code "42") (name "VCC5V-EXT") (class "Default")
      (node (ref "J1") (pin "1") (pinfunction "VCC_1") (pintype "passive"))
      (node (ref "J2") (pin "1") (pinfunction "1_1") (pintype "passive"))
      (node (ref "J3") (pin "1") (pinfunction "1_1") (pintype "passive"))
    )
    (net (code "43") (name "VCC5V-SAS") (class "Default")
      (node (ref "J3") (pin "3") (pinfunction "3_3") (pintype "passive"))
      (node (ref "J8") (pin "B16") (pinfunction "B16_B16") (pintype "passive"))
      (node (ref "J8") (pin "B17") (pinfunction "B17_B17") (pintype "passive"))
    )
    (net (code "44") (name "unconnected-(J1-D+-Pad3)") (class "Default")
      (node (ref "J1") (pin "3") (pinfunction "D+_3") (pintype "passive+no_connect"))
    )
    (net (code "45") (name "unconnected-(J1-D--Pad2)") (class "Default")
      (node (ref "J1") (pin "2") (pinfunction "D-_2") (pintype "passive+no_connect"))
    )
    (net (code "46") (name "unconnected-(J1-ID-Pad4)") (class "Default")
      (node (ref "J1") (pin "4") (pinfunction "ID_4") (pintype "passive+no_connect"))
    )
    (net (code "47") (name "unconnected-(J7-Pad23)") (class "Default")
      (node (ref "J7") (pin "23") (pinfunction "23_23") (pintype "passive+no_connect"))
    )
    (net (code "48") (name "unconnected-(J7-Pad24)") (class "Default")
      (node (ref "J7") (pin "24") (pinfunction "24_24") (pintype "passive+no_connect"))
    )
    (net (code "49") (name "unconnected-(J8-PadB8)") (class "Default")
      (node (ref "J8") (pin "B8") (pinfunction "B8_B8") (pintype "passive+no_connect"))
    )
    (net (code "50") (name "unconnected-(J8-PadB9)") (class "Default")
      (node (ref "J8") (pin "B9") (pinfunction "B9_B9") (pintype "passive+no_connect"))
    )
    (net (code "51") (name "unconnected-(J8-PadB10)") (class "Default")
      (node (ref "J8") (pin "B10") (pinfunction "B10_B10") (pintype "passive+no_connect"))
    )
    (net (code "52") (name "unconnected-(U1-NC-Pad13)") (class "Default")
      (node (ref "U1") (pin "13") (pinfunction "NC_13") (pintype "passive+no_connect"))
    )
    (net (code "53") (name "unconnected-(U2-~{FAULT}-Pad3)") (class "Default")
      (node (ref "U2") (pin "3") (pinfunction "~{FAULT}_3") (pintype "output+no_connect"))
    )
    (net (code "54") (name "unconnected-(U4-A4-Pad5)") (class "Default")
      (node (ref "U4") (pin "5") (pinfunction "A4_5") (pintype "bidirectional+no_connect"))
    )
    (net (code "55") (name "unconnected-(U4-B4-Pad7)") (class "Default")
      (node (ref "U4") (pin "7") (pinfunction "B4_7") (pintype "bidirectional+no_connect"))
    )
    (net (code "56") (name "unconnected-(X2-Pad1)") (class "Default")
      (node (ref "X2") (pin "1") (pinfunction "1_1") (pintype "passive+no_connect"))
    )
    (net (code "57") (name "unconnected-(X3-Pad1)") (class "Default")
      (node (ref "X3") (pin "1") (pinfunction "1_1") (pintype "passive+no_connect"))
    )
    (net (code "58") (name "unconnected-(X4-Pad1)") (class "Default")
      (node (ref "X4") (pin "1") (pinfunction "1_1") (pintype "passive+no_connect"))
    )
  )
)
